# breakout_blue.net
KiCad netlist of a schematic drawn in EAGLE
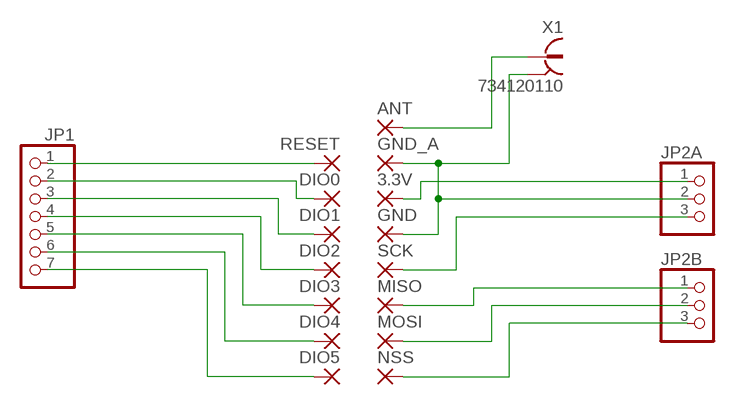
[diagram p0: schematic, sheet 1]

(export (version "E")
  (design (tool "Eeschema 10.0.6"))
  (components
    (comp (ref "3.3V")
      (value "SMD1")
      (footprint "eagle-import:SMD0,65-1,27")
      (libsource (lib "eagle-import") (part "SMD1"))
    )
    (comp (ref "ANT")
      (value "SMD1")
      (footprint "eagle-import:SMD0,65-1,27")
      (libsource (lib "eagle-import") (part "SMD1"))
    )
    (comp (ref "DIO0")
      (value "SMD1")
      (footprint "eagle-import:SMD0,65-1,27")
      (libsource (lib "eagle-import") (part "SMD1"))
    )
    (comp (ref "DIO1")
      (value "SMD1")
      (footprint "eagle-import:SMD0,65-1,27")
      (libsource (lib "eagle-import") (part "SMD1"))
    )
    (comp (ref "DIO2")
      (value "SMD1")
      (footprint "eagle-import:SMD0,65-1,27")
      (libsource (lib "eagle-import") (part "SMD1"))
    )
    (comp (ref "DIO3")
      (value "SMD1")
      (footprint "eagle-import:SMD0,65-1,27")
      (libsource (lib "eagle-import") (part "SMD1"))
    )
    (comp (ref "DIO4")
      (value "SMD1")
      (footprint "eagle-import:SMD0,65-1,27")
      (libsource (lib "eagle-import") (part "SMD1"))
    )
    (comp (ref "DIO5")
      (value "SMD1")
      (footprint "eagle-import:SMD0,65-1,27")
      (libsource (lib "eagle-import") (part "SMD1"))
    )
    (comp (ref "GND")
      (value "SMD1")
      (footprint "eagle-import:SMD0,65-1,27")
      (libsource (lib "eagle-import") (part "SMD1"))
    )
    (comp (ref "GND_A")
      (value "SMD1")
      (footprint "eagle-import:SMD0,65-1,27")
      (libsource (lib "eagle-import") (part "SMD1"))
    )
    (comp (ref "JP1")
      (value "PINHD-1X7")
      (footprint "eagle-import:1X07")
      (libsource (lib "eagle-import") (part "PINHD-1X7"))
    )
    (comp (ref "JP2A")
      (value "PINHD-1X3")
      (footprint "eagle-import:1X03")
      (libsource (lib "eagle-import") (part "PINHD-1X3"))
    )
    (comp (ref "JP2B")
      (value "PINHD-1X3")
      (footprint "eagle-import:1X03")
      (libsource (lib "eagle-import") (part "PINHD-1X3"))
    )
    (comp (ref "MISO")
      (value "SMD1")
      (footprint "eagle-import:SMD0,65-1,27")
      (libsource (lib "eagle-import") (part "SMD1"))
    )
    (comp (ref "MOSI")
      (value "SMD1")
      (footprint "eagle-import:SMD0,65-1,27")
      (libsource (lib "eagle-import") (part "SMD1"))
    )
    (comp (ref "NSS")
      (value "SMD1")
      (footprint "eagle-import:SMD0,65-1,27")
      (libsource (lib "eagle-import") (part "SMD1"))
    )
    (comp (ref "RESET")
      (value "SMD1")
      (footprint "eagle-import:SMD0,65-1,27")
      (libsource (lib "eagle-import") (part "SMD1"))
    )
    (comp (ref "SCK")
      (value "SMD1")
      (footprint "eagle-import:SMD0,65-1,27")
      (libsource (lib "eagle-import") (part "SMD1"))
    )
    (comp (ref "X1")
      (value "734120110")
      (footprint "eagle-import:734120110")
      (libsource (lib "eagle-import") (part "734120110"))
    )
  )
  (nets
    (net (code "1") (name "Net-(3.3V-P)") (class "Default")
      (node (ref "3.3V") (pin "1") (pinfunction "P_1") (pintype "passive"))
      (node (ref "JP2A") (pin "1") (pinfunction "1_1") (pintype "passive"))
    )
    (net (code "2") (name "Net-(ANT-P)") (class "Default")
      (node (ref "ANT") (pin "1") (pinfunction "P_1") (pintype "passive"))
      (node (ref "X1") (pin "1") (pinfunction "1_1") (pintype "passive"))
    )
    (net (code "3") (name "Net-(DIO0-P)") (class "Default")
      (node (ref "DIO0") (pin "1") (pinfunction "P_1") (pintype "passive"))
      (node (ref "JP1") (pin "2") (pinfunction "2_2") (pintype "passive"))
    )
    (net (code "4") (name "Net-(DIO1-P)") (class "Default")
      (node (ref "DIO1") (pin "1") (pinfunction "P_1") (pintype "passive"))
      (node (ref "JP1") (pin "3") (pinfunction "3_3") (pintype "passive"))
    )
    (net (code "5") (name "Net-(DIO2-P)") (class "Default")
      (node (ref "DIO2") (pin "1") (pinfunction "P_1") (pintype "passive"))
      (node (ref "JP1") (pin "4") (pinfunction "4_4") (pintype "passive"))
    )
    (net (code "6") (name "Net-(DIO3-P)") (class "Default")
      (node (ref "DIO3") (pin "1") (pinfunction "P_1") (pintype "passive"))
      (node (ref "JP1") (pin "5") (pinfunction "5_5") (pintype "passive"))
    )
    (net (code "7") (name "Net-(DIO4-P)") (class "Default")
      (node (ref "DIO4") (pin "1") (pinfunction "P_1") (pintype "passive"))
      (node (ref "JP1") (pin "6") (pinfunction "6_6") (pintype "passive"))
    )
    (net (code "8") (name "Net-(DIO5-P)") (class "Default")
      (node (ref "DIO5") (pin "1") (pinfunction "P_1") (pintype "passive"))
      (node (ref "JP1") (pin "7") (pinfunction "7_7") (pintype "passive"))
    )
    (net (code "9") (name "Net-(GND-P)") (class "Default")
      (node (ref "GND") (pin "1") (pinfunction "P_1") (pintype "passive"))
      (node (ref "GND_A") (pin "1") (pinfunction "P_1") (pintype "passive"))
      (node (ref "JP2A") (pin "2") (pinfunction "2_2") (pintype "passive"))
      (node (ref "X1") (pin "S@1") (pinfunction "2_S@1") (pintype "passive"))
      (node (ref "X1") (pin "S@2") (pinfunction "2_S@2") (pintype "passive"))
      (node (ref "X1") (pin "S@3") (pinfunction "2_S@3") (pintype "passive"))
    )
    (net (code "10") (name "Net-(MISO-P)") (class "Default")
      (node (ref "JP2B") (pin "1") (pinfunction "1_1") (pintype "passive"))
      (node (ref "MISO") (pin "1") (pinfunction "P_1") (pintype "passive"))
    )
    (net (code "11") (name "Net-(MOSI-P)") (class "Default")
      (node (ref "JP2B") (pin "2") (pinfunction "2_2") (pintype "passive"))
      (node (ref "MOSI") (pin "1") (pinfunction "P_1") (pintype "passive"))
    )
    (net (code "12") (name "Net-(NSS-P)") (class "Default")
      (node (ref "JP2B") (pin "3") (pinfunction "3_3") (pintype "passive"))
      (node (ref "NSS") (pin "1") (pinfunction "P_1") (pintype "passive"))
    )
    (net (code "13") (name "Net-(RESET-P)") (class "Default")
      (node (ref "JP1") (pin "1") (pinfunction "1_1") (pintype "passive"))
      (node (ref "RESET") (pin "1") (pinfunction "P_1") (pintype "passive"))
    )
    (net (code "14") (name "Net-(SCK-P)") (class "Default")
      (node (ref "JP2A") (pin "3") (pinfunction "3_3") (pintype "passive"))
      (node (ref "SCK") (pin "1") (pinfunction "P_1") (pintype "passive"))
    )
  )
)
